# MIDI.net
KiCad netlist of a schematic drawn in Altium Designer
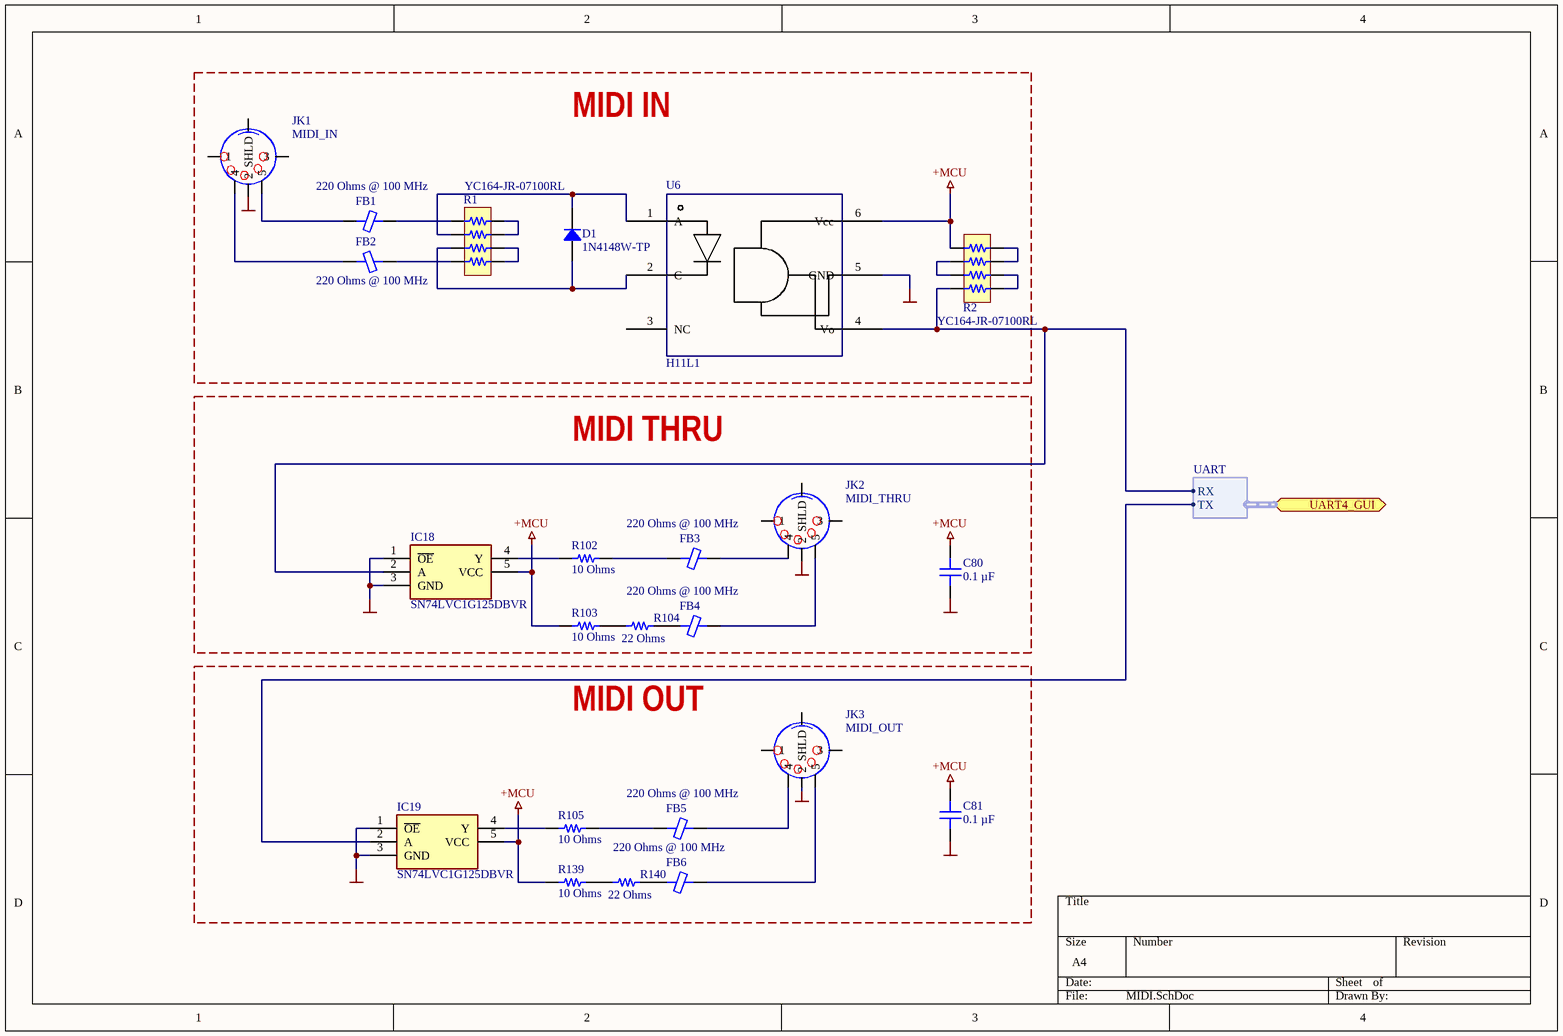
[diagram p0: MIDI.SchDoc]

(export (version "E")
  (design (tool "Eeschema 10.0.6"))
  (components
    (comp (ref "C80")
      (value "0.1 µF")
      (footprint "CAP 0603_1608")
      (description "CAP CER 0.1UF 50V X7R 0603")
      (fields (field (name "PART NUMBER") "C0603C104K5RAC7411") (field (name "MANUFACTURER") "KEMET"))
      (libsource (lib "Celestial Altium Library - altium_library") (part "Capacitor"))
    )
    (comp (ref "C81")
      (value "0.1 µF")
      (footprint "CAP 0603_1608")
      (description "CAP CER 0.1UF 50V X7R 0603")
      (fields (field (name "PART NUMBER") "C0603C104K5RAC7411") (field (name "MANUFACTURER") "KEMET"))
      (libsource (lib "Celestial Altium Library - altium_library") (part "Capacitor"))
    )
    (comp (ref "D1")
      (value "1N4148W-TP")
      (footprint "SOD-123")
      (description "DIODE GEN PURP 100V 150MA SOD123")
      (fields (field (name "MANUFACTURER") "Micro Commercial Co"))
      (libsource (lib "Celestial Altium Library - altium_library") (part "Diode"))
    )
    (comp (ref "FB1")
      (value "220 Ohms @ 100 MHz")
      (footprint "FER 0805_2012")
      (description "FERRITE BEAD 220 OHM 0805 1LN")
      (fields
        (field (name "PART NUMBER") "BLM21PG221SN1D")
        (field (name "MANUFACTURER") "Murata Electronics")
      )
      (libsource (lib "Celestial Altium Library - altium_library") (part "Ferrite Chip"))
    )
    (comp (ref "FB2")
      (value "220 Ohms @ 100 MHz")
      (footprint "FER 0805_2012")
      (description "FERRITE BEAD 220 OHM 0805 1LN")
      (fields
        (field (name "PART NUMBER") "BLM21PG221SN1D")
        (field (name "MANUFACTURER") "Murata Electronics")
      )
      (libsource (lib "Celestial Altium Library - altium_library") (part "Ferrite Chip"))
    )
    (comp (ref "FB3")
      (value "220 Ohms @ 100 MHz")
      (footprint "FER 0805_2012")
      (description "FERRITE BEAD 220 OHM 0805 1LN")
      (fields
        (field (name "PART NUMBER") "BLM21PG221SN1D")
        (field (name "MANUFACTURER") "Murata Electronics")
      )
      (libsource (lib "Celestial Altium Library - altium_library") (part "Ferrite Chip"))
    )
    (comp (ref "FB4")
      (value "220 Ohms @ 100 MHz")
      (footprint "FER 0805_2012")
      (description "FERRITE BEAD 220 OHM 0805 1LN")
      (fields
        (field (name "PART NUMBER") "BLM21PG221SN1D")
        (field (name "MANUFACTURER") "Murata Electronics")
      )
      (libsource (lib "Celestial Altium Library - altium_library") (part "Ferrite Chip"))
    )
    (comp (ref "FB5")
      (value "220 Ohms @ 100 MHz")
      (footprint "FER 0805_2012")
      (description "FERRITE BEAD 220 OHM 0805 1LN")
      (fields
        (field (name "PART NUMBER") "BLM21PG221SN1D")
        (field (name "MANUFACTURER") "Murata Electronics")
      )
      (libsource (lib "Celestial Altium Library - altium_library") (part "Ferrite Chip"))
    )
    (comp (ref "FB6")
      (value "220 Ohms @ 100 MHz")
      (footprint "FER 0805_2012")
      (description "FERRITE BEAD 220 OHM 0805 1LN")
      (fields
        (field (name "PART NUMBER") "BLM21PG221SN1D")
        (field (name "MANUFACTURER") "Murata Electronics")
      )
      (libsource (lib "Celestial Altium Library - altium_library") (part "Ferrite Chip"))
    )
    (comp (ref "IC18")
      (value "SN74LVC1G125DBVR")
      (footprint "ProtoStack_H750VBT:SOT95P280X145-5N")
      (description "Integrated Circuit")
      (fields (field (name "MOUSER PART NUMBER") "595-SN74LVC1G125DBVR"))
      (libsource (lib "ProtoStack_H750VBT") (part "SN74LVC1G125DBVR"))
    )
    (comp (ref "IC19")
      (value "SN74LVC1G125DBVR")
      (footprint "ProtoStack_H750VBT:SOT95P280X145-5N")
      (description "Integrated Circuit")
      (fields (field (name "MOUSER PART NUMBER") "595-SN74LVC1G125DBVR"))
      (libsource (lib "ProtoStack_H750VBT") (part "SN74LVC1G125DBVR"))
    )
    (comp (ref "JK1")
      (value "MIDI_IN")
      (footprint "DIN5")
      (description "DIN5")
      (libsource (lib "DAC_ADC") (part "DIN5"))
    )
    (comp (ref "JK2")
      (value "MIDI_THRU")
      (footprint "DIN5")
      (description "DIN5")
      (libsource (lib "DAC_ADC") (part "DIN5"))
    )
    (comp (ref "JK3")
      (value "MIDI_OUT")
      (footprint "DIN5")
      (description "DIN5")
      (libsource (lib "DAC_ADC") (part "DIN5"))
    )
    (comp (ref "R1")
      (value "YC164-JR-07100RL")
      (footprint "RESNET 1206-8 CONVEX")
      (description "RES ARRAY 4 RES 100 OHM 1206")
      (fields (field (name "MANUFACTURER") "Yageo") (field (name "TOLERANCE") "±5%"))
      (libsource (lib "") (part "Resistor Array (4 circuit)_1"))
    )
    (comp (ref "R2")
      (value "YC164-JR-07100RL")
      (footprint "RESNET 1206-8 CONVEX")
      (description "RES ARRAY 4 RES 100 OHM 1206")
      (fields (field (name "MANUFACTURER") "Yageo") (field (name "TOLERANCE") "±5%"))
      (libsource (lib "Celestial Altium Library - altium_library") (part "Resistor Array (4 circuit)"))
    )
    (comp (ref "R102")
      (value "10 Ohms")
      (footprint "RES 0603_1608")
      (description "RES SMD 10 OHM 1% 1/3W 0603")
      (fields
        (field (name "PART NUMBER") "ERJ-PA3F10R0V")
        (field (name "MANUFACTURER") "Panasonic Electronic Components")
      )
      (libsource (lib "Celestial Altium Library - altium_library") (part "Resistor"))
    )
    (comp (ref "R103")
      (value "10 Ohms")
      (footprint "RES 0603_1608")
      (description "RES SMD 10 OHM 1% 1/3W 0603")
      (fields
        (field (name "PART NUMBER") "ERJ-PA3F10R0V")
        (field (name "MANUFACTURER") "Panasonic Electronic Components")
      )
      (libsource (lib "Celestial Altium Library - altium_library") (part "Resistor"))
    )
    (comp (ref "R104")
      (value "22 Ohms")
      (footprint "RES 0402_1005")
      (description "RES 22 OHM 5% 1/16W 0402")
      (fields
        (field (name "PART NUMBER") "RMCF0402JT22R0")
        (field (name "MANUFACTURER") "Stackpole Electronics Inc")
      )
      (libsource (lib "Celestial Altium Library - altium_library") (part "Resistor"))
    )
    (comp (ref "R105")
      (value "10 Ohms")
      (footprint "RES 0603_1608")
      (description "RES SMD 10 OHM 1% 1/3W 0603")
      (fields
        (field (name "PART NUMBER") "ERJ-PA3F10R0V")
        (field (name "MANUFACTURER") "Panasonic Electronic Components")
      )
      (libsource (lib "Celestial Altium Library - altium_library") (part "Resistor"))
    )
    (comp (ref "R139")
      (value "10 Ohms")
      (footprint "RES 0603_1608")
      (description "RES SMD 10 OHM 1% 1/3W 0603")
      (fields
        (field (name "PART NUMBER") "ERJ-PA3F10R0V")
        (field (name "MANUFACTURER") "Panasonic Electronic Components")
      )
      (libsource (lib "Celestial Altium Library - altium_library") (part "Resistor"))
    )
    (comp (ref "R140")
      (value "22 Ohms")
      (footprint "RES 0402_1005")
      (description "RES 22 OHM 5% 1/16W 0402")
      (fields
        (field (name "PART NUMBER") "RMCF0402JT22R0")
        (field (name "MANUFACTURER") "Stackpole Electronics Inc")
      )
      (libsource (lib "Celestial Altium Library - altium_library") (part "Resistor"))
    )
    (comp (ref "U6")
      (value "H11L1")
      (footprint "SOIC254 DIP-6")
      (description "OPTOISO 4.17KV OPN COLL 6SMD")
      (libsource (lib "local_components") (part "H11L1SR2M"))
    )
  )
  (nets
    (net (code "2") (name "+MCU") (class "Default")
      (node (ref "C80") (pin "1") (pinfunction "1_1") (pintype "passive"))
      (node (ref "C81") (pin "1") (pinfunction "1_1") (pintype "passive"))
      (node (ref "IC18") (pin "5") (pinfunction "VCC_5") (pintype "passive"))
      (node (ref "IC19") (pin "5") (pinfunction "VCC_5") (pintype "passive"))
      (node (ref "R103") (pin "1") (pinfunction "1_1") (pintype "passive"))
      (node (ref "R139") (pin "1") (pinfunction "1_1") (pintype "passive"))
      (node (ref "R2") (pin "1") (pinfunction "1_1") (pintype "passive"))
      (node (ref "U6") (pin "6") (pinfunction "Vcc_6") (pintype "passive"))
    )
    (net (code "3") (name "/RX") (class "Default")
      (node (ref "IC18") (pin "2") (pinfunction "A_2") (pintype "passive"))
      (node (ref "R2") (pin "4") (pinfunction "4_4") (pintype "passive"))
      (node (ref "U6") (pin "4") (pinfunction "Vo_4") (pintype "passive"))
    )
    (net (code "4") (name "/TX") (class "Default")
      (node (ref "IC19") (pin "2") (pinfunction "A_2") (pintype "passive"))
    )
    (net (code "6") (name "GND") (class "Default")
      (node (ref "C80") (pin "2") (pinfunction "2_2") (pintype "passive"))
      (node (ref "C81") (pin "2") (pinfunction "2_2") (pintype "passive"))
      (node (ref "IC18") (pin "1") (pinfunction "~{OE}_1") (pintype "passive"))
      (node (ref "IC18") (pin "3") (pinfunction "GND_3") (pintype "passive"))
      (node (ref "IC19") (pin "1") (pinfunction "~{OE}_1") (pintype "passive"))
      (node (ref "IC19") (pin "3") (pinfunction "GND_3") (pintype "passive"))
      (node (ref "JK1") (pin "2") (pinfunction "2_2") (pintype "passive"))
      (node (ref "JK2") (pin "2") (pinfunction "2_2") (pintype "passive"))
      (node (ref "JK3") (pin "2") (pinfunction "2_2") (pintype "passive"))
      (node (ref "U6") (pin "5") (pinfunction "GND_5") (pintype "passive"))
    )
    (net (code "7") (name "Net-(FB1-Pad1)") (class "Default")
      (node (ref "FB1") (pin "1") (pinfunction "1_1") (pintype "passive"))
      (node (ref "JK1") (pin "5") (pinfunction "5_5") (pintype "passive"))
    )
    (net (code "8") (name "Net-(FB1-Pad2)") (class "Default")
      (node (ref "FB1") (pin "2") (pinfunction "2_2") (pintype "passive"))
      (node (ref "R1") (pin "5") (pinfunction "5_5") (pintype "passive"))
    )
    (net (code "9") (name "Net-(FB2-Pad1)") (class "Default")
      (node (ref "FB2") (pin "1") (pinfunction "1_1") (pintype "passive"))
      (node (ref "JK1") (pin "4") (pinfunction "4_4") (pintype "passive"))
    )
    (net (code "10") (name "Net-(FB2-Pad2)") (class "Default")
      (node (ref "FB2") (pin "2") (pinfunction "2_2") (pintype "passive"))
      (node (ref "R1") (pin "8") (pinfunction "8_8") (pintype "passive"))
    )
    (net (code "11") (name "Net-(FB3-Pad1)") (class "Default")
      (node (ref "FB3") (pin "1") (pinfunction "1_1") (pintype "passive"))
      (node (ref "R102") (pin "2") (pinfunction "2_2") (pintype "passive"))
    )
    (net (code "12") (name "Net-(FB3-Pad2)") (class "Default")
      (node (ref "FB3") (pin "2") (pinfunction "2_2") (pintype "passive"))
      (node (ref "JK2") (pin "4") (pinfunction "4_4") (pintype "passive"))
    )
    (net (code "13") (name "Net-(FB4-Pad1)") (class "Default")
      (node (ref "FB4") (pin "1") (pinfunction "1_1") (pintype "passive"))
      (node (ref "R104") (pin "2") (pinfunction "2_2") (pintype "passive"))
    )
    (net (code "14") (name "Net-(FB4-Pad2)") (class "Default")
      (node (ref "FB4") (pin "2") (pinfunction "2_2") (pintype "passive"))
      (node (ref "JK2") (pin "5") (pinfunction "5_5") (pintype "passive"))
    )
    (net (code "15") (name "Net-(FB5-Pad1)") (class "Default")
      (node (ref "FB5") (pin "1") (pinfunction "1_1") (pintype "passive"))
      (node (ref "R105") (pin "2") (pinfunction "2_2") (pintype "passive"))
    )
    (net (code "16") (name "Net-(FB5-Pad2)") (class "Default")
      (node (ref "FB5") (pin "2") (pinfunction "2_2") (pintype "passive"))
      (node (ref "JK3") (pin "4") (pinfunction "4_4") (pintype "passive"))
    )
    (net (code "17") (name "Net-(FB6-Pad1)") (class "Default")
      (node (ref "FB6") (pin "1") (pinfunction "1_1") (pintype "passive"))
      (node (ref "R140") (pin "2") (pinfunction "2_2") (pintype "passive"))
    )
    (net (code "18") (name "Net-(FB6-Pad2)") (class "Default")
      (node (ref "FB6") (pin "2") (pinfunction "2_2") (pintype "passive"))
      (node (ref "JK3") (pin "5") (pinfunction "5_5") (pintype "passive"))
    )
    (net (code "19") (name "Net-(IC18-Y)") (class "Default")
      (node (ref "IC18") (pin "4") (pinfunction "Y_4") (pintype "passive"))
      (node (ref "R102") (pin "1") (pinfunction "1_1") (pintype "passive"))
    )
    (net (code "20") (name "Net-(IC19-Y)") (class "Default")
      (node (ref "IC19") (pin "4") (pinfunction "Y_4") (pintype "passive"))
      (node (ref "R105") (pin "1") (pinfunction "1_1") (pintype "passive"))
    )
    (net (code "21") (name "Net-(R1-Pad1)") (class "Default")
      (node (ref "R1") (pin "1") (pinfunction "1_1") (pintype "passive"))
      (node (ref "R1") (pin "2") (pinfunction "2_2") (pintype "passive"))
    )
    (net (code "22") (name "Net-(R1-Pad3)") (class "Default")
      (node (ref "R1") (pin "3") (pinfunction "3_3") (pintype "passive"))
      (node (ref "R1") (pin "4") (pinfunction "4_4") (pintype "passive"))
    )
    (net (code "23") (name "Net-(R2-Pad2)") (class "Default")
      (node (ref "R2") (pin "2") (pinfunction "2_2") (pintype "passive"))
      (node (ref "R2") (pin "3") (pinfunction "3_3") (pintype "passive"))
    )
    (net (code "24") (name "Net-(R2-Pad5)") (class "Default")
      (node (ref "R2") (pin "5") (pinfunction "5_5") (pintype "passive"))
      (node (ref "R2") (pin "6") (pinfunction "6_6") (pintype "passive"))
    )
    (net (code "25") (name "Net-(R2-Pad7)") (class "Default")
      (node (ref "R2") (pin "7") (pinfunction "7_7") (pintype "passive"))
      (node (ref "R2") (pin "8") (pinfunction "8_8") (pintype "passive"))
    )
    (net (code "26") (name "Net-(R103-Pad2)") (class "Default")
      (node (ref "R103") (pin "2") (pinfunction "2_2") (pintype "passive"))
      (node (ref "R104") (pin "1") (pinfunction "1_1") (pintype "passive"))
    )
    (net (code "27") (name "Net-(R139-Pad2)") (class "Default")
      (node (ref "R139") (pin "2") (pinfunction "2_2") (pintype "passive"))
      (node (ref "R140") (pin "1") (pinfunction "1_1") (pintype "passive"))
    )
    (net (code "28") (name "Net-(U6-A)") (class "Default")
      (node (ref "D1") (pin "2") (pinfunction "2_2") (pintype "passive"))
      (node (ref "R1") (pin "6") (pinfunction "6_6") (pintype "passive"))
      (node (ref "U6") (pin "1") (pinfunction "A_1") (pintype "passive"))
    )
    (net (code "29") (name "Net-(U6-C)") (class "Default")
      (node (ref "D1") (pin "1") (pinfunction "1_1") (pintype "passive"))
      (node (ref "R1") (pin "7") (pinfunction "7_7") (pintype "passive"))
      (node (ref "U6") (pin "2") (pinfunction "C_2") (pintype "passive"))
    )
    (net (code "30") (name "unconnected-(JK1-Pad1)") (class "Default")
      (node (ref "JK1") (pin "1") (pinfunction "1_1") (pintype "passive"))
    )
    (net (code "31") (name "unconnected-(JK1-Pad3)") (class "Default")
      (node (ref "JK1") (pin "3") (pinfunction "3_3") (pintype "passive"))
    )
    (net (code "32") (name "unconnected-(JK1-SHLD-Pad6)") (class "Default")
      (node (ref "JK1") (pin "6") (pinfunction "SHLD_6") (pintype "passive"))
    )
    (net (code "33") (name "unconnected-(JK2-Pad1)") (class "Default")
      (node (ref "JK2") (pin "1") (pinfunction "1_1") (pintype "passive"))
    )
    (net (code "34") (name "unconnected-(JK2-Pad3)") (class "Default")
      (node (ref "JK2") (pin "3") (pinfunction "3_3") (pintype "passive"))
    )
    (net (code "35") (name "unconnected-(JK2-SHLD-Pad6)") (class "Default")
      (node (ref "JK2") (pin "6") (pinfunction "SHLD_6") (pintype "passive"))
    )
    (net (code "36") (name "unconnected-(JK3-Pad1)") (class "Default")
      (node (ref "JK3") (pin "1") (pinfunction "1_1") (pintype "passive"))
    )
    (net (code "37") (name "unconnected-(JK3-Pad3)") (class "Default")
      (node (ref "JK3") (pin "3") (pinfunction "3_3") (pintype "passive"))
    )
    (net (code "38") (name "unconnected-(JK3-SHLD-Pad6)") (class "Default")
      (node (ref "JK3") (pin "6") (pinfunction "SHLD_6") (pintype "passive"))
    )
    (net (code "39") (name "unconnected-(U6-NC-Pad3)") (class "Default")
      (node (ref "U6") (pin "3") (pinfunction "NC_3") (pintype "passive"))
    )
  )
)
